# Ext_Regulators.net
KiCad netlist of a schematic drawn in Altium Designer
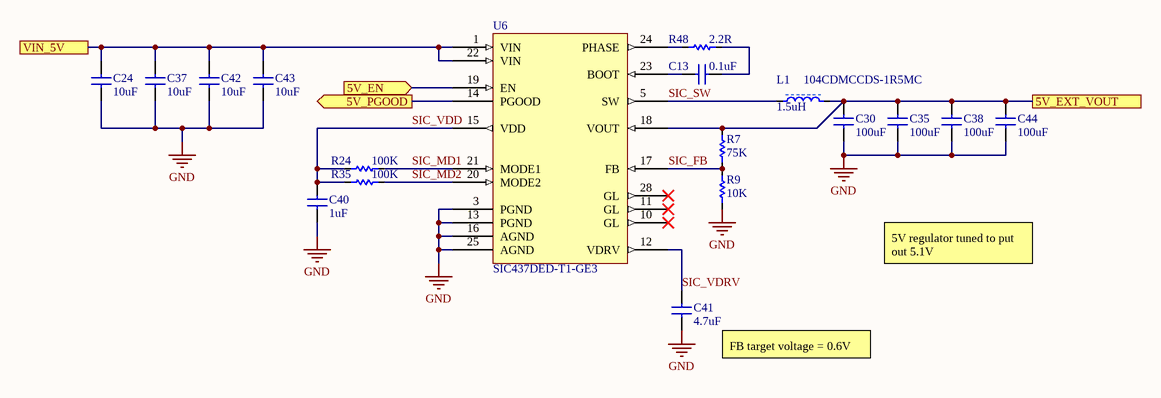
[diagram p0: Ext_Regulators.SchDoc]

(export (version "E")
  (design (tool "Eeschema 10.0.6"))
  (components
    (comp (ref "C13")
      (value "0.1uF")
      (footprint "0402_CAPACITOR")
      (description "CAP CERM 0.1uF 10% 16V 0402")
      (fields (field (name "VOLTAGE") "16V") (field (name "Comment") "CAP 0.1uF 16V X7R"))
      (libsource (lib "capacitor") (part "C_0402_0.1uF_16V_10%"))
    )
    (comp (ref "C24")
      (value "10uF")
      (footprint "0805_Capacitor")
      (description "CAP CER 10UF 25V X5R 0805")
      (fields (field (name "VOLTAGE") "25V") (field (name "Comment") "CAP 10uF 25V X5R"))
      (libsource (lib "capacitor") (part "C_0805_10uF_25V_10%"))
    )
    (comp (ref "C30")
      (value "100uF")
      (footprint "1210_Capacitor")
      (description "CAP CER 100UF 6.3V 20% X5R 1210")
      (fields (field (name "Comment") "C3225X5R0J107M250AC") (field (name "SVP CREATOR") "Spencer Berglund"))
      (libsource (lib "capacitor") (part "C_1210_100uF_6.3V_20%"))
    )
    (comp (ref "C35")
      (value "100uF")
      (footprint "1210_Capacitor")
      (description "CAP CER 100UF 6.3V 20% X5R 1210")
      (fields (field (name "Comment") "C3225X5R0J107M250AC") (field (name "SVP CREATOR") "Spencer Berglund"))
      (libsource (lib "capacitor") (part "C_1210_100uF_6.3V_20%"))
    )
    (comp (ref "C37")
      (value "10uF")
      (footprint "0805_Capacitor")
      (description "CAP CER 10UF 25V X5R 0805")
      (fields (field (name "VOLTAGE") "25V") (field (name "Comment") "CAP 10uF 25V X5R"))
      (libsource (lib "capacitor") (part "C_0805_10uF_25V_10%"))
    )
    (comp (ref "C38")
      (value "100uF")
      (footprint "1210_Capacitor")
      (description "CAP CER 100UF 6.3V 20% X5R 1210")
      (fields (field (name "Comment") "C3225X5R0J107M250AC") (field (name "SVP CREATOR") "Spencer Berglund"))
      (libsource (lib "capacitor") (part "C_1210_100uF_6.3V_20%"))
    )
    (comp (ref "C40")
      (value "1uF")
      (footprint "0603_CAPACITOR")
      (description "CAP CERM 1uF 10% 16V 0603")
      (fields
        (field (name "VOLTAGE") "16V")
        (field (name "Comment") "CAP 1uF 16V X7R")
        (field (name "SVP CREATOR") "Spencer Berglund")
      )
      (libsource (lib "capacitor") (part "C_0603_1uF_16V_10%"))
    )
    (comp (ref "C41")
      (value "4.7uF")
      (footprint "0805_Capacitor")
      (description "CAP CERM 4.7uF 10% 16V 0805")
      (fields
        (field (name "VOLTAGE") "16V")
        (field (name "Comment") "CAP 4.7uF 16V X5R")
        (field (name "SVP CREATOR") "Spencer Berglund")
      )
      (libsource (lib "capacitor") (part "C_0805_4.7uF_16V_10%"))
    )
    (comp (ref "C42")
      (value "10uF")
      (footprint "0805_Capacitor")
      (description "CAP CER 10UF 25V X5R 0805")
      (fields (field (name "VOLTAGE") "25V") (field (name "Comment") "CAP 10uF 25V X5R"))
      (libsource (lib "capacitor") (part "C_0805_10uF_25V_10%"))
    )
    (comp (ref "C43")
      (value "10uF")
      (footprint "0805_Capacitor")
      (description "CAP CER 10UF 25V X5R 0805")
      (fields (field (name "VOLTAGE") "25V") (field (name "Comment") "CAP 10uF 25V X5R"))
      (libsource (lib "capacitor") (part "C_0805_10uF_25V_10%"))
    )
    (comp (ref "C44")
      (value "100uF")
      (footprint "1210_Capacitor")
      (description "CAP CER 100UF 6.3V 20% X5R 1210")
      (fields (field (name "Comment") "C3225X5R0J107M250AC") (field (name "SVP CREATOR") "Spencer Berglund"))
      (libsource (lib "capacitor") (part "C_1210_100uF_6.3V_20%"))
    )
    (comp (ref "L1")
      (value "104CDMCCDS-1R5MC")
      (footprint "L_104CDMCCDS")
      (description "1.5µH Shielded Molded Inductor 19A 4.2mOhm Max Nonstandard")
      (fields
        (field (name "MANUFACTURER") "Sumida")
        (field (name "TOLERANCE") "20%")
        (field (name "ALTIUM_VALUE") "1.5uH")
      )
      (libsource (lib "inductor") (part "L_104CDMCCDS-1R5MC"))
    )
    (comp (ref "R7")
      (value "75K")
      (footprint "0402_Resistor")
      (description "Generic 0402 Resistor (10.2R to 10M)")
      (fields (field (name "TOLERANCE") "±1%") (field (name "MANUFACTURER") "Yageo"))
      (libsource (lib "resistor") (part "R_0402_generic_1%"))
    )
    (comp (ref "R9")
      (value "10K")
      (footprint "0402_Resistor")
      (description "Generic 0402 Resistor (10.2R to 10M)")
      (fields (field (name "TOLERANCE") "±1%") (field (name "MANUFACTURER") "Yageo"))
      (libsource (lib "resistor") (part "R_0402_generic_1%"))
    )
    (comp (ref "R24")
      (value "100K")
      (footprint "0402_Resistor")
      (description "Generic 0402 Resistor (10.2R to 10M)")
      (fields (field (name "TOLERANCE") "±1%") (field (name "MANUFACTURER") "Yageo"))
      (libsource (lib "resistor") (part "R_0402_generic_1%"))
    )
    (comp (ref "R35")
      (value "100K")
      (footprint "0402_Resistor")
      (description "Generic 0402 Resistor (10.2R to 10M)")
      (fields (field (name "TOLERANCE") "±1%") (field (name "MANUFACTURER") "Yageo"))
      (libsource (lib "resistor") (part "R_0402_generic_1%"))
    )
    (comp (ref "R48")
      (value "2.2R")
      (footprint "0402_Resistor")
      (description "Generic 0402 Resistor (10.2R to 10M)")
      (fields (field (name "TOLERANCE") "±1%") (field (name "MANUFACTURER") "Yageo"))
      (libsource (lib "resistor") (part "R_0402_generic_1%"))
    )
    (comp (ref "U6")
      (value "SIC437DED-T1-GE3")
      (footprint "U_MLP44-24L")
      (description "Buck Switching Regulator IC Positive Adjustable 0.6V 1 Output 12A 24-PowerWFQFN")
      (fields (field (name "MANUFACTURER") "Vishay"))
      (libsource (lib "ic") (part "U_SIC437DED"))
    )
  )
  (nets
    (net (code "1") (name "/5V_EN") (class "Default")
      (node (ref "U6") (pin "19") (pinfunction "EN_19") (pintype "input"))
    )
    (net (code "2") (name "/5V_EXT_VOUT") (class "Default")
      (node (ref "C30") (pin "1") (pinfunction "1_1") (pintype "passive"))
      (node (ref "C35") (pin "1") (pinfunction "1_1") (pintype "passive"))
      (node (ref "C38") (pin "1") (pinfunction "1_1") (pintype "passive"))
      (node (ref "C44") (pin "1") (pinfunction "1_1") (pintype "passive"))
      (node (ref "L1") (pin "2") (pinfunction "2_2") (pintype "passive"))
      (node (ref "R7") (pin "2") (pinfunction "2_2") (pintype "passive"))
      (node (ref "U6") (pin "18") (pinfunction "VOUT_18") (pintype "input"))
    )
    (net (code "3") (name "/5V_PGOOD") (class "Default")
      (node (ref "U6") (pin "14") (pinfunction "PGOOD_14") (pintype "open_collector"))
    )
    (net (code "4") (name "/SIC_FB") (class "Default")
      (node (ref "R7") (pin "1") (pinfunction "1_1") (pintype "passive"))
      (node (ref "R9") (pin "2") (pinfunction "2_2") (pintype "passive"))
      (node (ref "U6") (pin "17") (pinfunction "FB_17") (pintype "input"))
    )
    (net (code "5") (name "/SIC_MD1") (class "Default")
      (node (ref "R24") (pin "1") (pinfunction "1_1") (pintype "passive"))
      (node (ref "U6") (pin "21") (pinfunction "MODE1_21") (pintype "input"))
    )
    (net (code "6") (name "/SIC_MD2") (class "Default")
      (node (ref "R35") (pin "1") (pinfunction "1_1") (pintype "passive"))
      (node (ref "U6") (pin "20") (pinfunction "MODE2_20") (pintype "input"))
    )
    (net (code "7") (name "/SIC_SW") (class "Default")
      (node (ref "L1") (pin "1") (pinfunction "1_1") (pintype "passive"))
      (node (ref "U6") (pin "5") (pinfunction "SW_5") (pintype "output"))
    )
    (net (code "8") (name "/SIC_VDD") (class "Default")
      (node (ref "C40") (pin "1") (pinfunction "1_1") (pintype "passive"))
      (node (ref "R24") (pin "2") (pinfunction "2_2") (pintype "passive"))
      (node (ref "R35") (pin "2") (pinfunction "2_2") (pintype "passive"))
      (node (ref "U6") (pin "15") (pinfunction "VDD_15") (pintype "output"))
    )
    (net (code "9") (name "/SIC_VDRV") (class "Default")
      (node (ref "C41") (pin "1") (pinfunction "1_1") (pintype "passive"))
      (node (ref "U6") (pin "12") (pinfunction "VDRV_12") (pintype "output"))
    )
    (net (code "10") (name "/VIN_5V") (class "Default")
      (node (ref "C24") (pin "1") (pinfunction "1_1") (pintype "passive"))
      (node (ref "C37") (pin "1") (pinfunction "1_1") (pintype "passive"))
      (node (ref "C42") (pin "1") (pinfunction "1_1") (pintype "passive"))
      (node (ref "C43") (pin "1") (pinfunction "1_1") (pintype "passive"))
      (node (ref "U6") (pin "1") (pinfunction "VIN_1") (pintype "input"))
      (node (ref "U6") (pin "22") (pinfunction "VIN_22") (pintype "input"))
    )
    (net (code "11") (name "GND") (class "Default")
      (node (ref "C24") (pin "2") (pinfunction "2_2") (pintype "passive"))
      (node (ref "C30") (pin "2") (pinfunction "2_2") (pintype "passive"))
      (node (ref "C35") (pin "2") (pinfunction "2_2") (pintype "passive"))
      (node (ref "C37") (pin "2") (pinfunction "2_2") (pintype "passive"))
      (node (ref "C38") (pin "2") (pinfunction "2_2") (pintype "passive"))
      (node (ref "C40") (pin "2") (pinfunction "2_2") (pintype "passive"))
      (node (ref "C41") (pin "2") (pinfunction "2_2") (pintype "passive"))
      (node (ref "C42") (pin "2") (pinfunction "2_2") (pintype "passive"))
      (node (ref "C43") (pin "2") (pinfunction "2_2") (pintype "passive"))
      (node (ref "C44") (pin "2") (pinfunction "2_2") (pintype "passive"))
      (node (ref "R9") (pin "1") (pinfunction "1_1") (pintype "passive"))
      (node (ref "U6") (pin "13") (pinfunction "PGND_13") (pintype "power_in"))
      (node (ref "U6") (pin "16") (pinfunction "AGND_16") (pintype "power_in"))
      (node (ref "U6") (pin "25") (pinfunction "AGND_25") (pintype "power_in"))
      (node (ref "U6") (pin "3") (pinfunction "PGND_3") (pintype "power_in"))
    )
    (net (code "12") (name "Net-(C13-Pad1)") (class "Default")
      (node (ref "C13") (pin "1") (pinfunction "1_1") (pintype "passive"))
      (node (ref "R48") (pin "2") (pinfunction "2_2") (pintype "passive"))
    )
    (net (code "13") (name "Net-(U6-BOOT)") (class "Default")
      (node (ref "C13") (pin "2") (pinfunction "2_2") (pintype "passive"))
      (node (ref "U6") (pin "23") (pinfunction "BOOT_23") (pintype "input"))
    )
    (net (code "14") (name "Net-(U6-PHASE)") (class "Default")
      (node (ref "R48") (pin "1") (pinfunction "1_1") (pintype "passive"))
      (node (ref "U6") (pin "24") (pinfunction "PHASE_24") (pintype "output"))
    )
    (net (code "15") (name "unconnected-(U6-GL-Pad10)") (class "Default")
      (node (ref "U6") (pin "10") (pinfunction "GL_10") (pintype "output+no_connect"))
    )
    (net (code "16") (name "unconnected-(U6-GL-Pad11)") (class "Default")
      (node (ref "U6") (pin "11") (pinfunction "GL_11") (pintype "output+no_connect"))
    )
    (net (code "17") (name "unconnected-(U6-GL-Pad28)") (class "Default")
      (node (ref "U6") (pin "28") (pinfunction "GL_28") (pintype "output+no_connect"))
    )
  )
)
